# SENSOR.net
KiCad netlist of a schematic drawn in Altium Designer
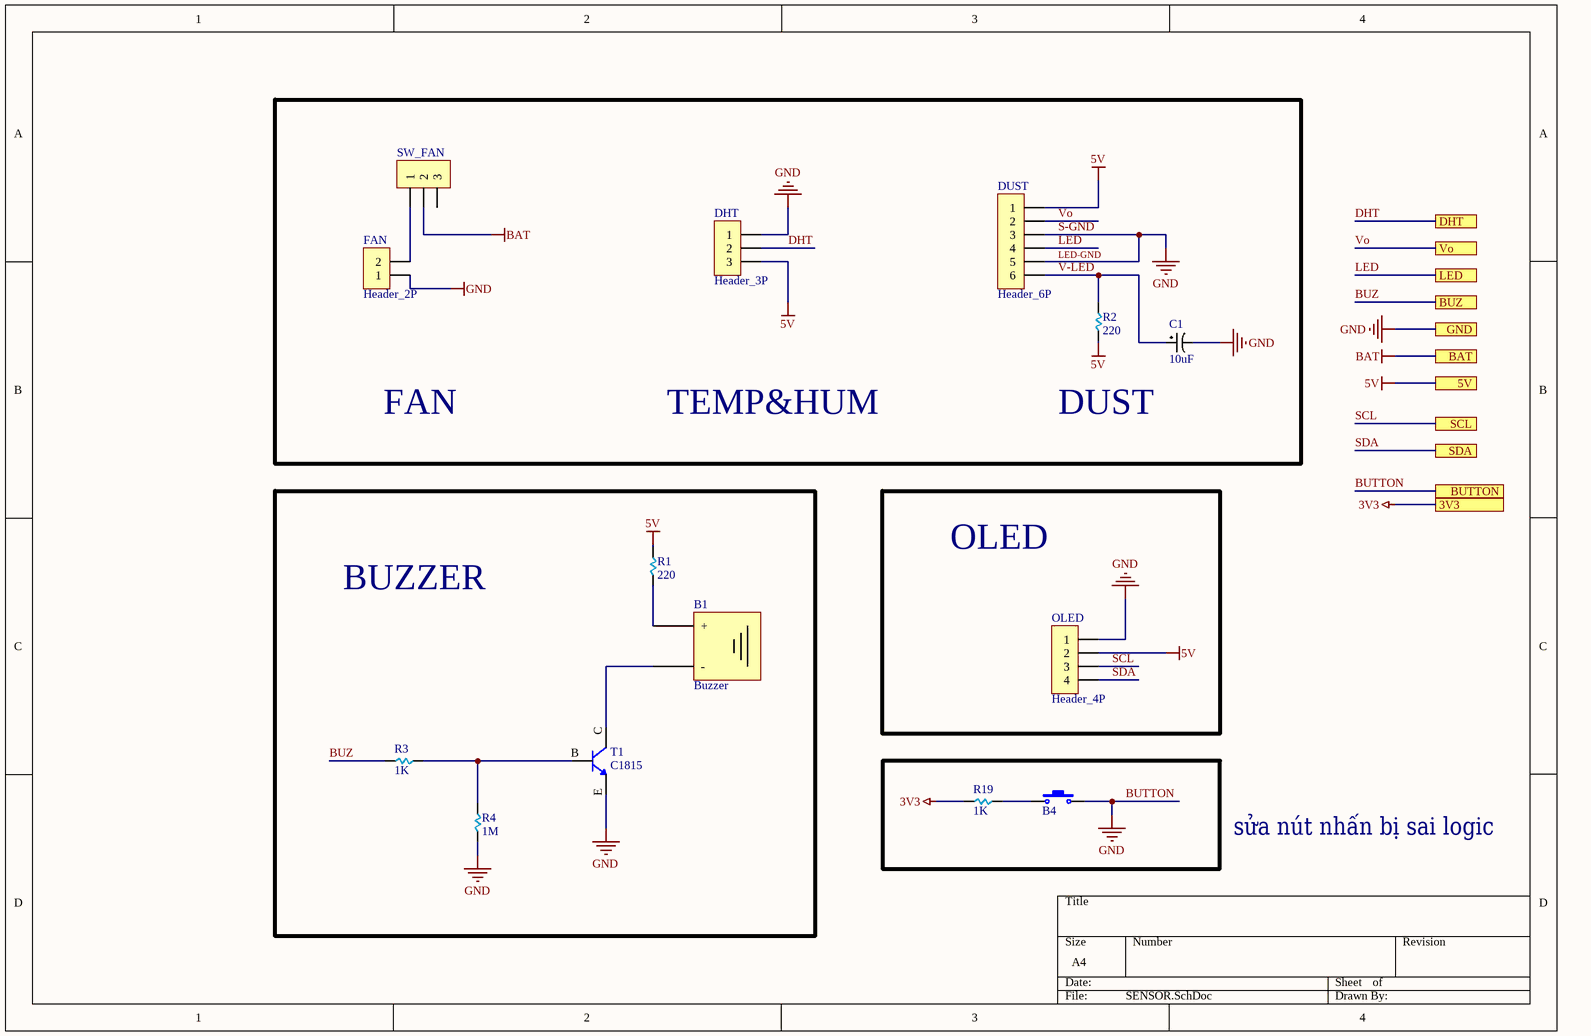
[diagram p0: SENSOR.SchDoc]

(export (version "E")
  (design (tool "Eeschema 10.0.6"))
  (components
    (comp (ref "B1") (value "Buzzer") (footprint "Buzzer") (libsource (lib "KM_ALTIUM") (part "Buzzer")))
    (comp (ref "B4")
      (value "BUTTON")
      (footprint "BUTTON 3x4x2")
      (libsource (lib "KM_ALTIUM") (part "BUTTON"))
    )
    (comp (ref "C1") (value "10uF") (footprint "CAP 5x11") (libsource (lib "KM_ALTIUM") (part "Cap_P")))
    (comp (ref "DHT")
      (value "Header_3P")
      (footprint "3P_1.5_V")
      (libsource (lib "KM_ALTIUM") (part "Header_3P"))
    )
    (comp (ref "DUST")
      (value "Header_6P")
      (footprint "6P_1.5_V")
      (libsource (lib "KM_ALTIUM") (part "Header_6P"))
    )
    (comp (ref "FAN")
      (value "Header_2P")
      (footprint "2P_1.5_V")
      (libsource (lib "KM_ALTIUM") (part "Header_2P"))
    )
    (comp (ref "OLED")
      (value "Header_4P")
      (footprint "4P_1.5_V")
      (libsource (lib "KM_ALTIUM") (part "Header_4P"))
    )
    (comp (ref "R1") (value "220") (footprint "RES 0603") (libsource (lib "KM_ALTIUM") (part "RES")))
    (comp (ref "R2") (value "220") (footprint "RES 0603") (libsource (lib "KM_ALTIUM") (part "RES")))
    (comp (ref "R3") (value "1K") (footprint "RES 0603") (libsource (lib "KM_ALTIUM") (part "RES")))
    (comp (ref "R4") (value "1M") (footprint "RES 0603") (libsource (lib "KM_ALTIUM") (part "RES")))
    (comp (ref "R19") (value "1K") (footprint "RES 0603") (libsource (lib "KM_ALTIUM") (part "RES")))
    (comp (ref "SW_FAN")
      (value "SWITCH")
      (footprint "Switch SK12D07")
      (libsource (lib "KM_ALTIUM") (part "SWITCH"))
    )
    (comp (ref "T1") (value "C1815") (footprint "C1815") (libsource (lib "KM_ALTIUM") (part "C1815")))
  )
  (nets
    (net (code "1") (name "/BUZ") (class "Default")
      (node (ref "R3") (pin "1") (pinfunction "1_1") (pintype "passive"))
    )
    (net (code "2") (name "/DHT") (class "Default")
      (node (ref "DHT") (pin "2") (pinfunction "2_2") (pintype "passive"))
    )
    (net (code "3") (name "/LED") (class "Default")
      (node (ref "DUST") (pin "4") (pinfunction "4_4") (pintype "passive"))
    )
    (net (code "4") (name "/SCL") (class "Default")
      (node (ref "OLED") (pin "3") (pinfunction "3_3") (pintype "passive"))
    )
    (net (code "5") (name "/SDA") (class "Default")
      (node (ref "OLED") (pin "4") (pinfunction "4_4") (pintype "passive"))
    )
    (net (code "6") (name "/V-LED") (class "Default")
      (node (ref "C1") (pin "1") (pinfunction "1_1") (pintype "passive"))
      (node (ref "DUST") (pin "6") (pinfunction "6_6") (pintype "passive"))
      (node (ref "R2") (pin "1") (pinfunction "1_1") (pintype "passive"))
    )
    (net (code "7") (name "/Vo") (class "Default")
      (node (ref "DUST") (pin "2") (pinfunction "2_2") (pintype "passive"))
    )
    (net (code "8") (name "3V3") (class "Default")
      (node (ref "R19") (pin "2") (pinfunction "2_2") (pintype "passive"))
    )
    (net (code "9") (name "5V") (class "Default")
      (node (ref "DHT") (pin "3") (pinfunction "3_3") (pintype "passive"))
      (node (ref "DUST") (pin "1") (pinfunction "1_1") (pintype "passive"))
      (node (ref "OLED") (pin "2") (pinfunction "2_2") (pintype "passive"))
      (node (ref "R1") (pin "1") (pinfunction "1_1") (pintype "passive"))
      (node (ref "R2") (pin "2") (pinfunction "2_2") (pintype "passive"))
    )
    (net (code "10") (name "BAT") (class "Default")
      (node (ref "SW_FAN") (pin "2") (pinfunction "2_2") (pintype "passive"))
    )
    (net (code "11") (name "GND") (class "Default")
      (node (ref "B4") (pin "2") (pinfunction "2_2") (pintype "passive"))
      (node (ref "C1") (pin "2") (pinfunction "2_2") (pintype "passive"))
      (node (ref "DHT") (pin "1") (pinfunction "1_1") (pintype "passive"))
      (node (ref "DUST") (pin "3") (pinfunction "3_3") (pintype "passive"))
      (node (ref "DUST") (pin "5") (pinfunction "5_5") (pintype "passive"))
      (node (ref "FAN") (pin "1") (pinfunction "1_1") (pintype "passive"))
      (node (ref "OLED") (pin "1") (pinfunction "1_1") (pintype "passive"))
      (node (ref "R4") (pin "2") (pinfunction "2_2") (pintype "passive"))
      (node (ref "T1") (pin "E") (pinfunction "E_E") (pintype "passive"))
    )
    (net (code "12") (name "Net-(B1-Pad+)") (class "Default")
      (node (ref "B1") (pin "+") (pinfunction "+_+") (pintype "passive"))
      (node (ref "R1") (pin "2") (pinfunction "2_2") (pintype "passive"))
    )
    (net (code "13") (name "Net-(B1-Pad-)") (class "Default")
      (node (ref "B1") (pin "-") (pinfunction "-_-") (pintype "passive"))
      (node (ref "T1") (pin "C") (pinfunction "C_C") (pintype "passive"))
    )
    (net (code "14") (name "Net-(B4-Pad1)") (class "Default")
      (node (ref "B4") (pin "1") (pinfunction "1_1") (pintype "passive"))
      (node (ref "R19") (pin "1") (pinfunction "1_1") (pintype "passive"))
    )
    (net (code "15") (name "Net-(FAN-Pad2)") (class "Default")
      (node (ref "FAN") (pin "2") (pinfunction "2_2") (pintype "passive"))
      (node (ref "SW_FAN") (pin "1") (pinfunction "1_1") (pintype "passive"))
    )
    (net (code "16") (name "Net-(R3-Pad2)") (class "Default")
      (node (ref "R3") (pin "2") (pinfunction "2_2") (pintype "passive"))
      (node (ref "R4") (pin "1") (pinfunction "1_1") (pintype "passive"))
      (node (ref "T1") (pin "B") (pinfunction "B_B") (pintype "passive"))
    )
    (net (code "17") (name "unconnected-(SW_FAN-Pad3)") (class "Default")
      (node (ref "SW_FAN") (pin "3") (pinfunction "3_3") (pintype "passive"))
    )
  )
)
